# tamiya_camrobo_face.net
KiCad netlist of a schematic drawn in EAGLE
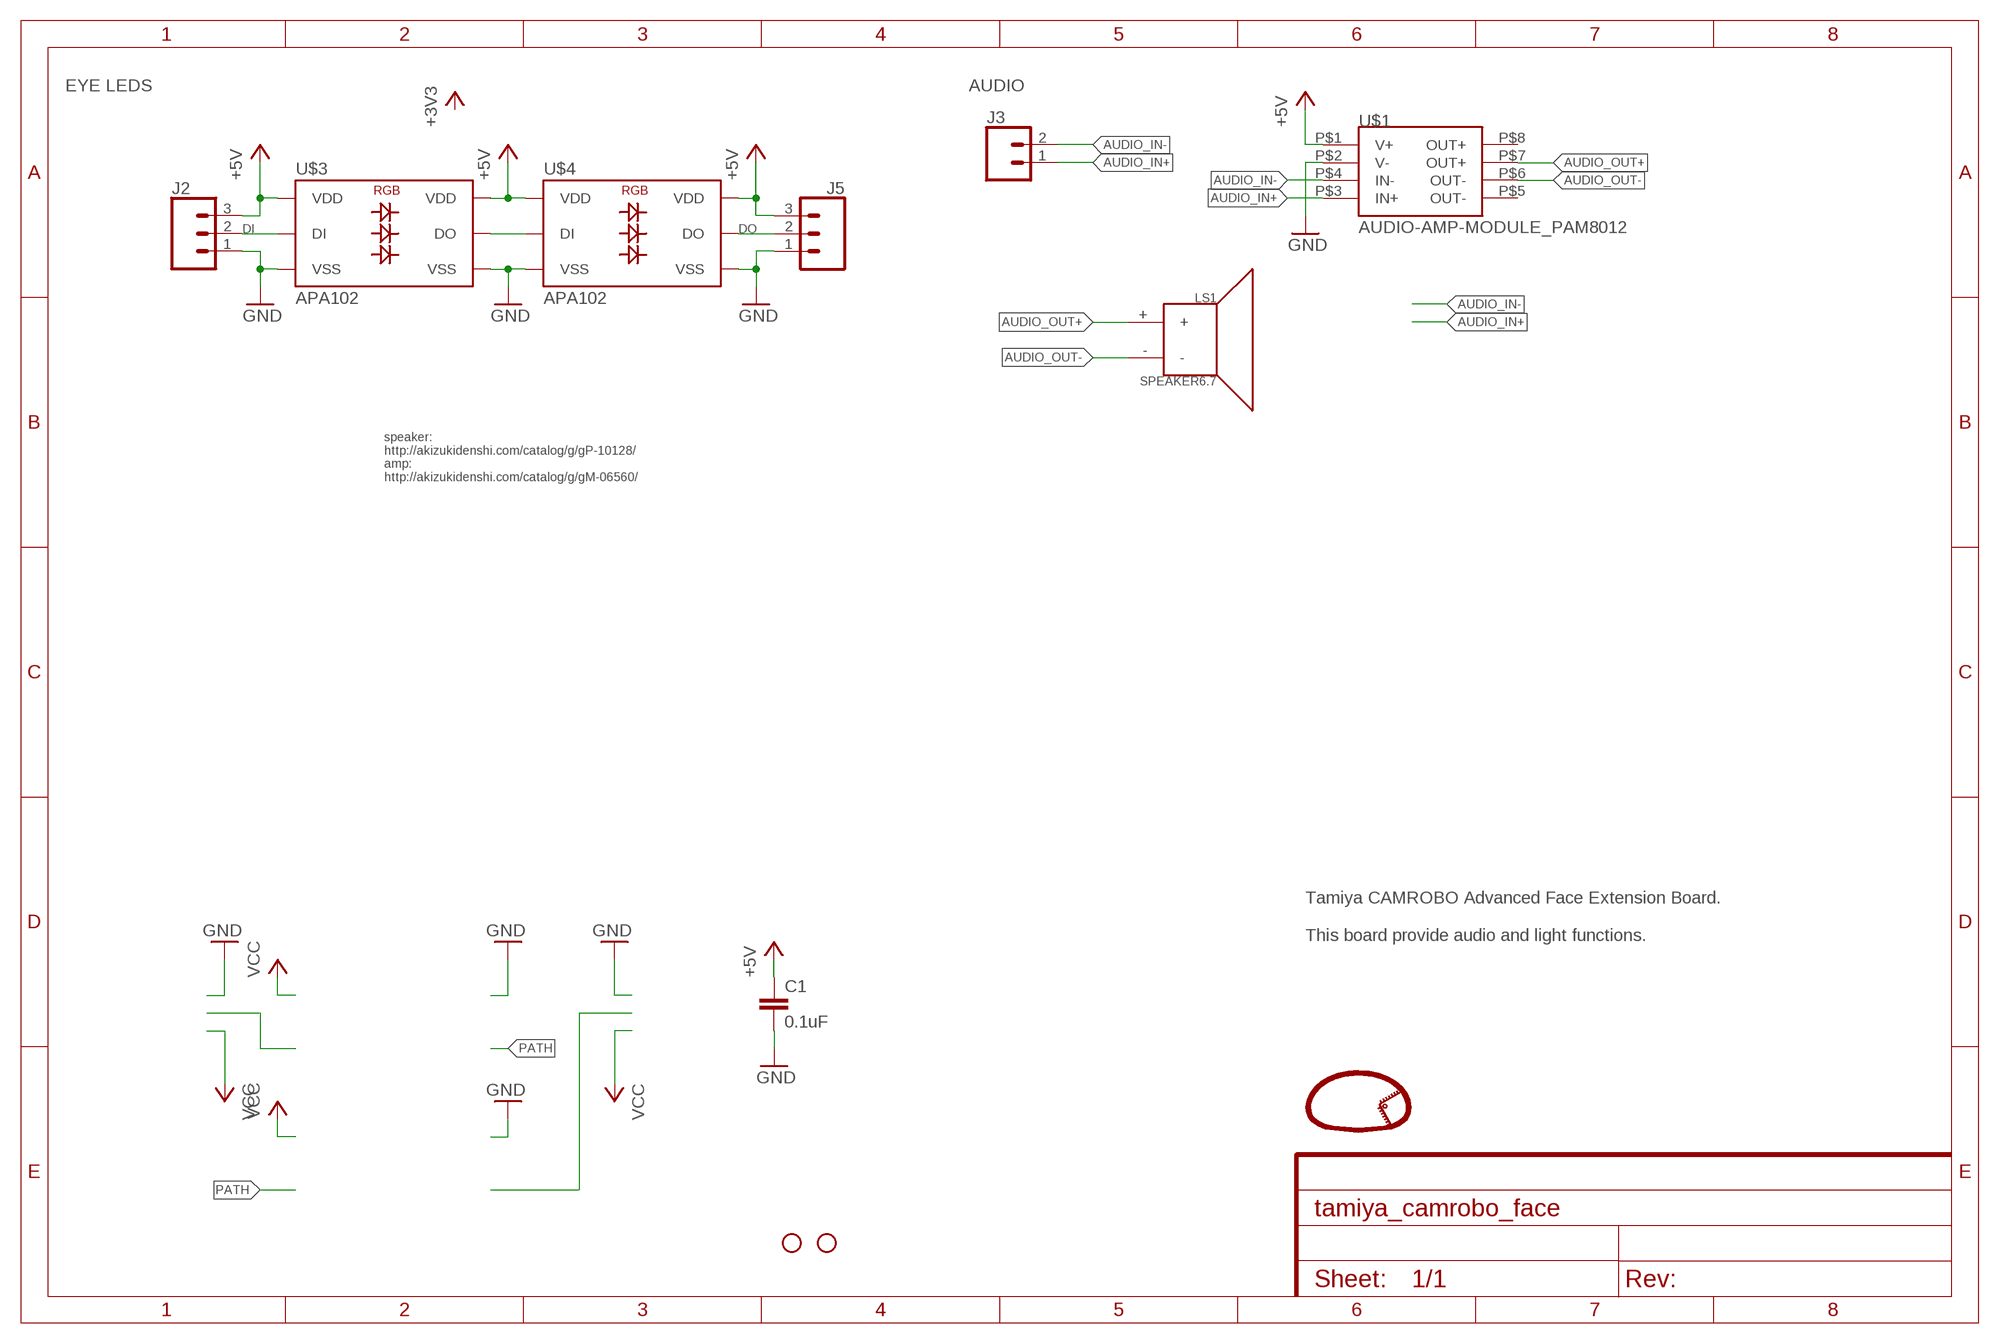
[diagram p0: schematic, sheet 1]

(export (version "E")
  (design (tool "Eeschema 10.0.6"))
  (components
    (comp (ref "C1")
      (value "0.1uF")
      (footprint "eagle-import:CAP-PTH-SMALL-KIT")
      (libsource (lib "eagle-import") (part "0.1UF-KIT-EZ-50V-20%"))
    )
    (comp (ref "H1")
      (value "STAND-OFF")
      (footprint "eagle-import:STAND-OFF")
      (libsource (lib "eagle-import") (part "STAND-OFF"))
    )
    (comp (ref "H2")
      (value "STAND-OFF")
      (footprint "eagle-import:STAND-OFF")
      (libsource (lib "eagle-import") (part "STAND-OFF"))
    )
    (comp (ref "J2")
      (value "CONN_03")
      (footprint "eagle-import:1X03")
      (libsource (lib "eagle-import") (part "CONN_03"))
    )
    (comp (ref "J3")
      (value "CONN_02")
      (footprint "eagle-import:1X02")
      (libsource (lib "eagle-import") (part "CONN_02"))
    )
    (comp (ref "J5")
      (value "CONN_03")
      (footprint "eagle-import:1X03")
      (libsource (lib "eagle-import") (part "CONN_03"))
    )
    (comp (ref "LS1")
      (value "SPEAKER6.7")
      (footprint "eagle-import:SPEAKER-6.7MM")
      (libsource (lib "eagle-import") (part "SPEAKER6.7"))
    )
    (comp (ref "U$1")
      (value "AUDIO-AMP-MODULE_PAM8012")
      (footprint "eagle-import:AE-PAM8012")
      (libsource (lib "eagle-import") (part "AUDIO-AMP-MODULE_PAM8012"))
    )
    (comp (ref "U$2")
      (value "LOGO")
      (footprint "eagle-import:LOGO")
      (libsource (lib "eagle-import") (part "LOGO"))
    )
    (comp (ref "U$3")
      (value "APA102")
      (footprint "eagle-import:APA102-STRIP-ELEMENT")
      (libsource (lib "eagle-import") (part "APA102"))
    )
    (comp (ref "U$4")
      (value "APA102")
      (footprint "eagle-import:APA102-STRIP-ELEMENT")
      (libsource (lib "eagle-import") (part "APA102"))
    )
  )
  (nets
    (net (code "2") (name "+5V") (class "Default")
      (node (ref "C1") (pin "1") (pinfunction "1_1") (pintype "passive"))
      (node (ref "J2") (pin "3") (pinfunction "3_3") (pintype "passive"))
      (node (ref "J5") (pin "3") (pinfunction "3_3") (pintype "passive"))
      (node (ref "U$1") (pin "P$1") (pinfunction "V+_P$1") (pintype "power_in"))
      (node (ref "U$3") (pin "P$1") (pinfunction "VDD_P$1") (pintype "power_in"))
      (node (ref "U$3") (pin "P$6") (pinfunction "VDD_P$6") (pintype "power_in"))
      (node (ref "U$4") (pin "P$1") (pinfunction "VDD_P$1") (pintype "power_in"))
      (node (ref "U$4") (pin "P$6") (pinfunction "VDD_P$6") (pintype "power_in"))
    )
    (net (code "3") (name "/DI") (class "Default")
      (node (ref "J2") (pin "2") (pinfunction "2_2") (pintype "passive"))
      (node (ref "U$3") (pin "P$5") (pinfunction "DI_P$5") (pintype "input"))
    )
    (net (code "4") (name "/DO") (class "Default")
      (node (ref "J5") (pin "2") (pinfunction "2_2") (pintype "passive"))
      (node (ref "U$4") (pin "P$2") (pinfunction "DO_P$2") (pintype "output"))
    )
    (net (code "5") (name "AUDIO_IN+") (class "Default")
      (node (ref "J3") (pin "1") (pinfunction "1_1") (pintype "passive"))
      (node (ref "U$1") (pin "P$3") (pinfunction "IN+_P$3") (pintype "input"))
    )
    (net (code "6") (name "AUDIO_IN-") (class "Default")
      (node (ref "J3") (pin "2") (pinfunction "2_2") (pintype "passive"))
      (node (ref "U$1") (pin "P$4") (pinfunction "IN-_P$4") (pintype "input"))
    )
    (net (code "7") (name "AUDIO_OUT+") (class "Default")
      (node (ref "LS1") (pin "+") (pinfunction "+_+") (pintype "bidirectional"))
      (node (ref "U$1") (pin "P$7") (pinfunction "OUT+_P$7") (pintype "output"))
    )
    (net (code "8") (name "AUDIO_OUT-") (class "Default")
      (node (ref "LS1") (pin "-") (pinfunction "-_-") (pintype "bidirectional"))
      (node (ref "U$1") (pin "P$6") (pinfunction "OUT-_P$6") (pintype "output"))
    )
    (net (code "9") (name "GND") (class "Default")
      (node (ref "C1") (pin "2") (pinfunction "2_2") (pintype "passive"))
      (node (ref "J2") (pin "1") (pinfunction "1_1") (pintype "passive"))
      (node (ref "J5") (pin "1") (pinfunction "1_1") (pintype "passive"))
      (node (ref "U$1") (pin "P$2") (pinfunction "V-_P$2") (pintype "power_in"))
      (node (ref "U$3") (pin "P$3") (pinfunction "VSS_P$3") (pintype "power_in"))
      (node (ref "U$3") (pin "P$4") (pinfunction "VSS_P$4") (pintype "power_in"))
      (node (ref "U$4") (pin "P$3") (pinfunction "VSS_P$3") (pintype "power_in"))
      (node (ref "U$4") (pin "P$4") (pinfunction "VSS_P$4") (pintype "power_in"))
    )
    (net (code "10") (name "Net-(U$3-DO)") (class "Default")
      (node (ref "U$3") (pin "P$2") (pinfunction "DO_P$2") (pintype "output"))
      (node (ref "U$4") (pin "P$5") (pinfunction "DI_P$5") (pintype "input"))
    )
    (net (code "13") (name "unconnected-(U$1-OUT+-PadP$8)") (class "Default")
      (node (ref "U$1") (pin "P$8") (pinfunction "OUT+_P$8") (pintype "output"))
    )
    (net (code "14") (name "unconnected-(U$1-OUT--PadP$5)") (class "Default")
      (node (ref "U$1") (pin "P$5") (pinfunction "OUT-_P$5") (pintype "output"))
    )
  )
)
